# ArduinoPhoneChargeCircuit.net
KiCad netlist of a schematic drawn in EAGLE
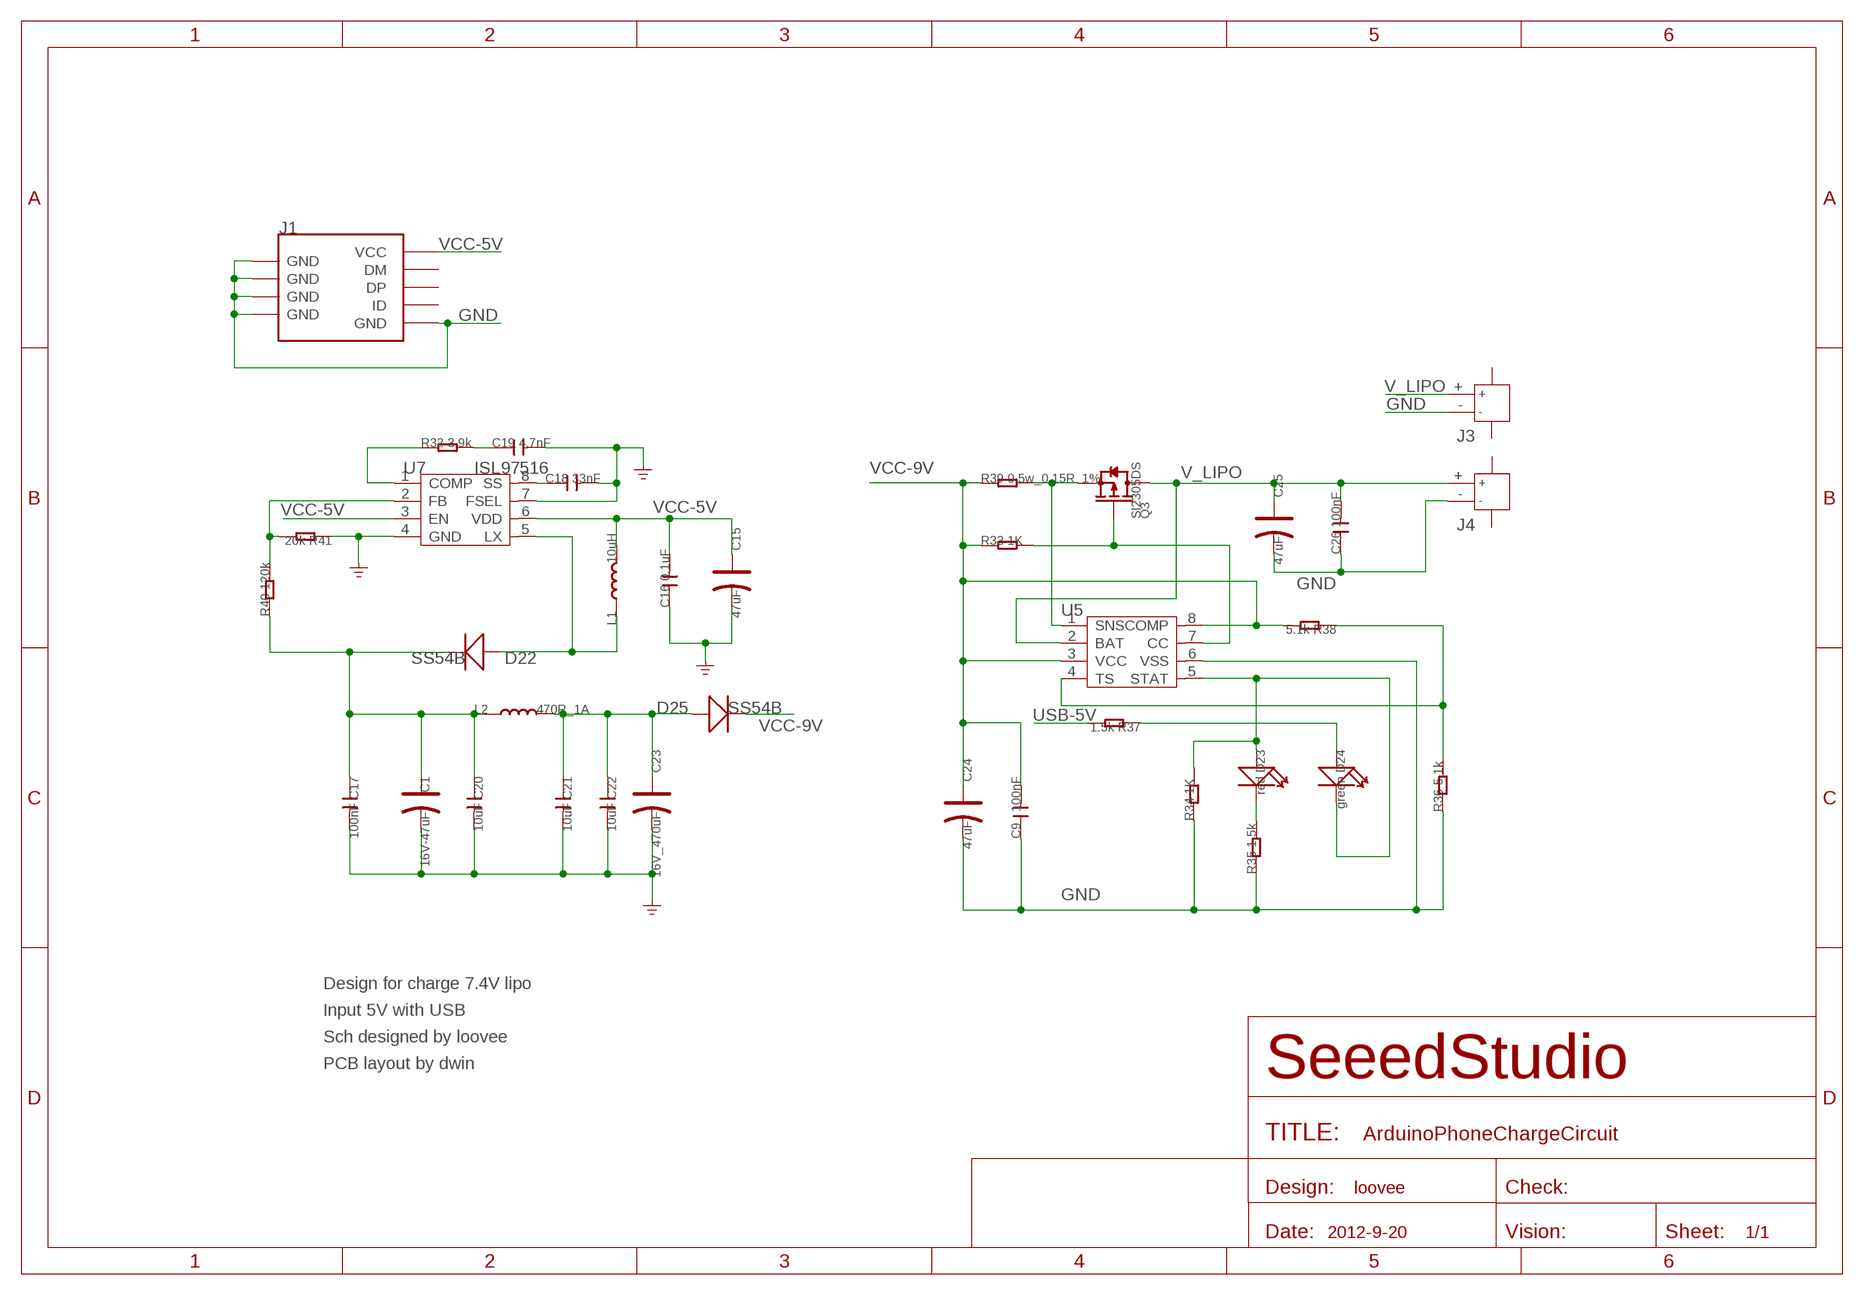
[diagram p0: schematic, sheet 1]

(export (version "E")
  (design (tool "Eeschema 10.0.6"))
  (components
    (comp (ref "C1")
      (value "16V-47uF")
      (footprint "eagle-import:AVX-C")
      (libsource (lib "eagle-import") (part "CAP-AVX-C"))
    )
    (comp (ref "C9")
      (value "100nF")
      (footprint "eagle-import:0805")
      (libsource (lib "eagle-import") (part "C-0805"))
    )
    (comp (ref "C15")
      (value "47uF")
      (footprint "eagle-import:1210")
      (libsource (lib "eagle-import") (part "CAP-1210"))
    )
    (comp (ref "C16")
      (value "0.1uF")
      (footprint "eagle-import:0603")
      (libsource (lib "eagle-import") (part "C-0603"))
    )
    (comp (ref "C17")
      (value "100nF")
      (footprint "eagle-import:0603")
      (libsource (lib "eagle-import") (part "C-0603"))
    )
    (comp (ref "C18")
      (value "33nF")
      (footprint "eagle-import:0603")
      (libsource (lib "eagle-import") (part "C-0603"))
    )
    (comp (ref "C19")
      (value "4.7nF")
      (footprint "eagle-import:0603")
      (libsource (lib "eagle-import") (part "C-0603"))
    )
    (comp (ref "C20")
      (value "10uF")
      (footprint "eagle-import:0805")
      (libsource (lib "eagle-import") (part "C-0805"))
    )
    (comp (ref "C21")
      (value "10uF")
      (footprint "eagle-import:0805")
      (libsource (lib "eagle-import") (part "C-0805"))
    )
    (comp (ref "C22")
      (value "10uF")
      (footprint "eagle-import:0805")
      (libsource (lib "eagle-import") (part "C-0805"))
    )
    (comp (ref "C23")
      (value "16V_470uF")
      (footprint "eagle-import:AVX-E")
      (libsource (lib "eagle-import") (part "CAP-AVX-E"))
    )
    (comp (ref "C24")
      (value "47uF")
      (footprint "eagle-import:AVX-C")
      (libsource (lib "eagle-import") (part "CAP-AVX-C"))
    )
    (comp (ref "C25")
      (value "47uF")
      (footprint "eagle-import:AVX-A")
      (libsource (lib "eagle-import") (part "CAP-AVX-A"))
    )
    (comp (ref "C26")
      (value "100nF")
      (footprint "eagle-import:0805")
      (libsource (lib "eagle-import") (part "C-0805"))
    )
    (comp (ref "D22")
      (value "SS54B")
      (footprint "eagle-import:SMB")
      (libsource (lib "eagle-import") (part "D'MBRS240LT3'"))
    )
    (comp (ref "D23")
      (value "red")
      (footprint "eagle-import:LED-2P-2.54-3MM")
      (libsource (lib "eagle-import") (part "LED-3MM"))
    )
    (comp (ref "D24")
      (value "green")
      (footprint "eagle-import:LED-2P-2.54-3MM")
      (libsource (lib "eagle-import") (part "LED-3MM"))
    )
    (comp (ref "D25")
      (value "SS54B")
      (footprint "eagle-import:SMB")
      (libsource (lib "eagle-import") (part "D'MBRS240LT3'"))
    )
    (comp (ref "J1")
      (value "USB-MINIUSB-5P-STRONG")
      (footprint "eagle-import:MINI-SMD-5P")
      (libsource (lib "eagle-import") (part "USB-MINIUSB-5P-STRONG"))
    )
    (comp (ref "J3")
      (value "JACK-JST-2P-SMD-PW'2.0'")
      (footprint "eagle-import:JST-SMD-2.0-90D")
      (libsource (lib "eagle-import") (part "JACK-JST-2P-SMD-PW'2.0'"))
    )
    (comp (ref "J4")
      (value "JACK-JST-2P-SMD-PW'2.0'")
      (footprint "eagle-import:JST-SMD-2.0-90D")
      (libsource (lib "eagle-import") (part "JACK-JST-2P-SMD-PW'2.0'"))
    )
    (comp (ref "L1")
      (value "10uH")
      (footprint "eagle-import:2626")
      (libsource (lib "eagle-import") (part "L'IHLP-2525BD-01'"))
    )
    (comp (ref "L2")
      (value "470R_1A")
      (footprint "eagle-import:L0805")
      (libsource (lib "eagle-import") (part "L'0805'"))
    )
    (comp (ref "Q3")
      (value "SI2305DS")
      (footprint "eagle-import:SOT23")
      (libsource (lib "eagle-import") (part "MOSFET-P'SI2323CDS/SI2305DS{lt}BR{gt}'"))
    )
    (comp (ref "R32")
      (value "3.9k")
      (footprint "eagle-import:R0603")
      (libsource (lib "eagle-import") (part "R-0603"))
    )
    (comp (ref "R33")
      (value "1K")
      (footprint "eagle-import:R0805")
      (libsource (lib "eagle-import") (part "R-0805"))
    )
    (comp (ref "R34")
      (value "1K")
      (footprint "eagle-import:R0805")
      (libsource (lib "eagle-import") (part "R-0805"))
    )
    (comp (ref "R35")
      (value "1.5k")
      (footprint "eagle-import:R0805")
      (libsource (lib "eagle-import") (part "R-0805"))
    )
    (comp (ref "R36")
      (value "5.1k")
      (footprint "eagle-import:R0805")
      (libsource (lib "eagle-import") (part "R-0805"))
    )
    (comp (ref "R37")
      (value "1.5k")
      (footprint "eagle-import:R0805")
      (libsource (lib "eagle-import") (part "R-0805"))
    )
    (comp (ref "R38")
      (value "5.1k")
      (footprint "eagle-import:R0805")
      (libsource (lib "eagle-import") (part "R-0805"))
    )
    (comp (ref "R39")
      (value "0.5w_0.15R 1%")
      (footprint "eagle-import:R2512")
      (libsource (lib "eagle-import") (part "R-2512"))
    )
    (comp (ref "R40")
      (value "120k")
      (footprint "eagle-import:R0603")
      (libsource (lib "eagle-import") (part "R-0603"))
    )
    (comp (ref "R41")
      (value "20k")
      (footprint "eagle-import:R0603")
      (libsource (lib "eagle-import") (part "R-0603"))
    )
    (comp (ref "U5")
      (value "BQ2057WPW")
      (footprint "eagle-import:TSSOP8")
      (libsource (lib "eagle-import") (part "BQ2057WPW"))
    )
    (comp (ref "U7")
      (value "ISL97516")
      (footprint "eagle-import:MSOP8")
      (libsource (lib "eagle-import") (part "ISL97516"))
    )
  )
  (nets
    (net (code "1") (name "/USB-5V") (class "Default")
      (node (ref "R37") (pin "2") (pinfunction "2_2") (pintype "passive"))
    )
    (net (code "2") (name "/VCC-5V") (class "Default")
      (node (ref "C15") (pin "+") (pinfunction "+_+") (pintype "passive"))
      (node (ref "C16") (pin "2") (pinfunction "2_2") (pintype "passive"))
      (node (ref "J1") (pin "1") (pinfunction "VCC_1") (pintype "bidirectional"))
      (node (ref "L1") (pin "2") (pinfunction "2_2") (pintype "passive"))
      (node (ref "U7") (pin "3") (pinfunction "EN_3") (pintype "input"))
      (node (ref "U7") (pin "6") (pinfunction "VDD_6") (pintype "power_in"))
    )
    (net (code "3") (name "/VCC-9V") (class "Default")
      (node (ref "C24") (pin "+") (pinfunction "+_+") (pintype "passive"))
      (node (ref "C9") (pin "2") (pinfunction "2_2") (pintype "passive"))
      (node (ref "D25") (pin "-") (pinfunction "-_-") (pintype "passive"))
      (node (ref "R33") (pin "1") (pinfunction "1_1") (pintype "passive"))
      (node (ref "R38") (pin "2") (pinfunction "2_2") (pintype "passive"))
      (node (ref "R39") (pin "1") (pinfunction "1_1") (pintype "passive"))
      (node (ref "U5") (pin "3") (pinfunction "VCC_3") (pintype "input"))
      (node (ref "U5") (pin "8") (pinfunction "COMP_8") (pintype "input"))
    )
    (net (code "4") (name "/V_LIPO") (class "Default")
      (node (ref "C25") (pin "+") (pinfunction "+_+") (pintype "passive"))
      (node (ref "C26") (pin "2") (pinfunction "2_2") (pintype "passive"))
      (node (ref "J3") (pin "+") (pinfunction "1_+") (pintype "bidirectional"))
      (node (ref "J4") (pin "+") (pinfunction "1_+") (pintype "bidirectional"))
      (node (ref "Q3") (pin "3") (pinfunction "D_3") (pintype "passive"))
      (node (ref "U5") (pin "2") (pinfunction "BAT_2") (pintype "input"))
    )
    (net (code "5") (name "GND_POWER") (class "Default")
      (node (ref "C1") (pin "-") (pinfunction "-_-") (pintype "passive"))
      (node (ref "C15") (pin "-") (pinfunction "-_-") (pintype "passive"))
      (node (ref "C16") (pin "1") (pinfunction "1_1") (pintype "passive"))
      (node (ref "C17") (pin "2") (pinfunction "2_2") (pintype "passive"))
      (node (ref "C18") (pin "2") (pinfunction "2_2") (pintype "passive"))
      (node (ref "C19") (pin "2") (pinfunction "2_2") (pintype "passive"))
      (node (ref "C20") (pin "2") (pinfunction "2_2") (pintype "passive"))
      (node (ref "C21") (pin "2") (pinfunction "2_2") (pintype "passive"))
      (node (ref "C22") (pin "2") (pinfunction "2_2") (pintype "passive"))
      (node (ref "C23") (pin "-") (pinfunction "-_-") (pintype "passive"))
      (node (ref "C24") (pin "-") (pinfunction "-_-") (pintype "passive"))
      (node (ref "C25") (pin "-") (pinfunction "-_-") (pintype "passive"))
      (node (ref "C26") (pin "1") (pinfunction "1_1") (pintype "passive"))
      (node (ref "C9") (pin "1") (pinfunction "1_1") (pintype "passive"))
      (node (ref "J1") (pin "5") (pinfunction "GND_5") (pintype "bidirectional"))
      (node (ref "J1") (pin "GND@1") (pinfunction "GND_GND@1") (pintype "bidirectional"))
      (node (ref "J1") (pin "GND@2") (pinfunction "GND_GND@2") (pintype "bidirectional"))
      (node (ref "J1") (pin "GND@3") (pinfunction "GND_GND@3") (pintype "bidirectional"))
      (node (ref "J1") (pin "GND@4") (pinfunction "GND_GND@4") (pintype "bidirectional"))
      (node (ref "J3") (pin "-") (pinfunction "2_-") (pintype "bidirectional"))
      (node (ref "J4") (pin "-") (pinfunction "2_-") (pintype "bidirectional"))
      (node (ref "R34") (pin "1") (pinfunction "1_1") (pintype "passive"))
      (node (ref "R35") (pin "1") (pinfunction "1_1") (pintype "passive"))
      (node (ref "R36") (pin "1") (pinfunction "1_1") (pintype "passive"))
      (node (ref "R41") (pin "1") (pinfunction "1_1") (pintype "passive"))
      (node (ref "U5") (pin "6") (pinfunction "VSS_6") (pintype "power_in"))
      (node (ref "U7") (pin "4") (pinfunction "GND_4") (pintype "power_in"))
      (node (ref "U7") (pin "7") (pinfunction "FSEL_7") (pintype "bidirectional"))
    )
    (net (code "6") (name "Net-(C1-Pad+)") (class "Default")
      (node (ref "C1") (pin "+") (pinfunction "+_+") (pintype "passive"))
      (node (ref "C17") (pin "1") (pinfunction "1_1") (pintype "passive"))
      (node (ref "C20") (pin "1") (pinfunction "1_1") (pintype "passive"))
      (node (ref "D22") (pin "-") (pinfunction "-_-") (pintype "passive"))
      (node (ref "L2") (pin "1") (pinfunction "1_1") (pintype "passive"))
      (node (ref "R40") (pin "1") (pinfunction "1_1") (pintype "passive"))
    )
    (net (code "7") (name "Net-(C19-Pad1)") (class "Default")
      (node (ref "C19") (pin "1") (pinfunction "1_1") (pintype "passive"))
      (node (ref "R32") (pin "2") (pinfunction "2_2") (pintype "passive"))
    )
    (net (code "8") (name "Net-(C21-Pad1)") (class "Default")
      (node (ref "C21") (pin "1") (pinfunction "1_1") (pintype "passive"))
      (node (ref "C22") (pin "1") (pinfunction "1_1") (pintype "passive"))
      (node (ref "C23") (pin "+") (pinfunction "+_+") (pintype "passive"))
      (node (ref "D25") (pin "+") (pinfunction "+_+") (pintype "passive"))
      (node (ref "L2") (pin "2") (pinfunction "2_2") (pintype "passive"))
    )
    (net (code "9") (name "Net-(D23-+)") (class "Default")
      (node (ref "D23") (pin "A") (pinfunction "+_A") (pintype "passive"))
      (node (ref "D24") (pin "K") (pinfunction "-_K") (pintype "passive"))
      (node (ref "R34") (pin "2") (pinfunction "2_2") (pintype "passive"))
      (node (ref "U5") (pin "5") (pinfunction "STAT_5") (pintype "output"))
    )
    (net (code "10") (name "Net-(D23--)") (class "Default")
      (node (ref "D23") (pin "K") (pinfunction "-_K") (pintype "passive"))
      (node (ref "R35") (pin "2") (pinfunction "2_2") (pintype "passive"))
    )
    (net (code "11") (name "Net-(D24-+)") (class "Default")
      (node (ref "D24") (pin "A") (pinfunction "+_A") (pintype "passive"))
      (node (ref "R37") (pin "1") (pinfunction "1_1") (pintype "passive"))
    )
    (net (code "12") (name "Net-(Q3-G)") (class "Default")
      (node (ref "Q3") (pin "1") (pinfunction "G_1") (pintype "passive"))
      (node (ref "R33") (pin "2") (pinfunction "2_2") (pintype "passive"))
      (node (ref "U5") (pin "7") (pinfunction "CC_7") (pintype "output"))
    )
    (net (code "13") (name "Net-(Q3-S)") (class "Default")
      (node (ref "Q3") (pin "2") (pinfunction "S_2") (pintype "passive"))
      (node (ref "R39") (pin "2") (pinfunction "2_2") (pintype "passive"))
      (node (ref "U5") (pin "1") (pinfunction "SNS_1") (pintype "input"))
    )
    (net (code "14") (name "Net-(U5-TS)") (class "Default")
      (node (ref "R36") (pin "2") (pinfunction "2_2") (pintype "passive"))
      (node (ref "R38") (pin "1") (pinfunction "1_1") (pintype "passive"))
      (node (ref "U5") (pin "4") (pinfunction "TS_4") (pintype "input"))
    )
    (net (code "15") (name "Net-(U7-COMP)") (class "Default")
      (node (ref "R32") (pin "1") (pinfunction "1_1") (pintype "passive"))
      (node (ref "U7") (pin "1") (pinfunction "COMP_1") (pintype "bidirectional"))
    )
    (net (code "16") (name "Net-(U7-FB)") (class "Default")
      (node (ref "R40") (pin "2") (pinfunction "2_2") (pintype "passive"))
      (node (ref "R41") (pin "2") (pinfunction "2_2") (pintype "passive"))
      (node (ref "U7") (pin "2") (pinfunction "FB_2") (pintype "input"))
    )
    (net (code "17") (name "Net-(U7-LX)") (class "Default")
      (node (ref "D22") (pin "+") (pinfunction "+_+") (pintype "passive"))
      (node (ref "L1") (pin "1") (pinfunction "1_1") (pintype "passive"))
      (node (ref "U7") (pin "5") (pinfunction "LX_5") (pintype "output"))
    )
    (net (code "18") (name "Net-(U7-SS)") (class "Default")
      (node (ref "C18") (pin "1") (pinfunction "1_1") (pintype "passive"))
      (node (ref "U7") (pin "8") (pinfunction "SS_8") (pintype "bidirectional"))
    )
    (net (code "19") (name "unconnected-(J1-DM-Pad2)") (class "Default")
      (node (ref "J1") (pin "2") (pinfunction "DM_2") (pintype "bidirectional"))
    )
    (net (code "20") (name "unconnected-(J1-DP-Pad3)") (class "Default")
      (node (ref "J1") (pin "3") (pinfunction "DP_3") (pintype "bidirectional"))
    )
    (net (code "21") (name "unconnected-(J1-ID-Pad4)") (class "Default")
      (node (ref "J1") (pin "4") (pinfunction "ID_4") (pintype "bidirectional"))
    )
    (net (code "22") (name "unconnected-(J3-Pad3)") (class "Default")
      (node (ref "J3") (pin "3") (pinfunction "3_3") (pintype "bidirectional"))
    )
    (net (code "23") (name "unconnected-(J3-Pad4)") (class "Default")
      (node (ref "J3") (pin "4") (pinfunction "4_4") (pintype "bidirectional"))
    )
    (net (code "24") (name "unconnected-(J4-Pad3)") (class "Default")
      (node (ref "J4") (pin "3") (pinfunction "3_3") (pintype "bidirectional"))
    )
    (net (code "25") (name "unconnected-(J4-Pad4)") (class "Default")
      (node (ref "J4") (pin "4") (pinfunction "4_4") (pintype "bidirectional"))
    )
  )
)
